# Morpheus_NDO.net
KiCad netlist of a schematic drawn in Altium Designer
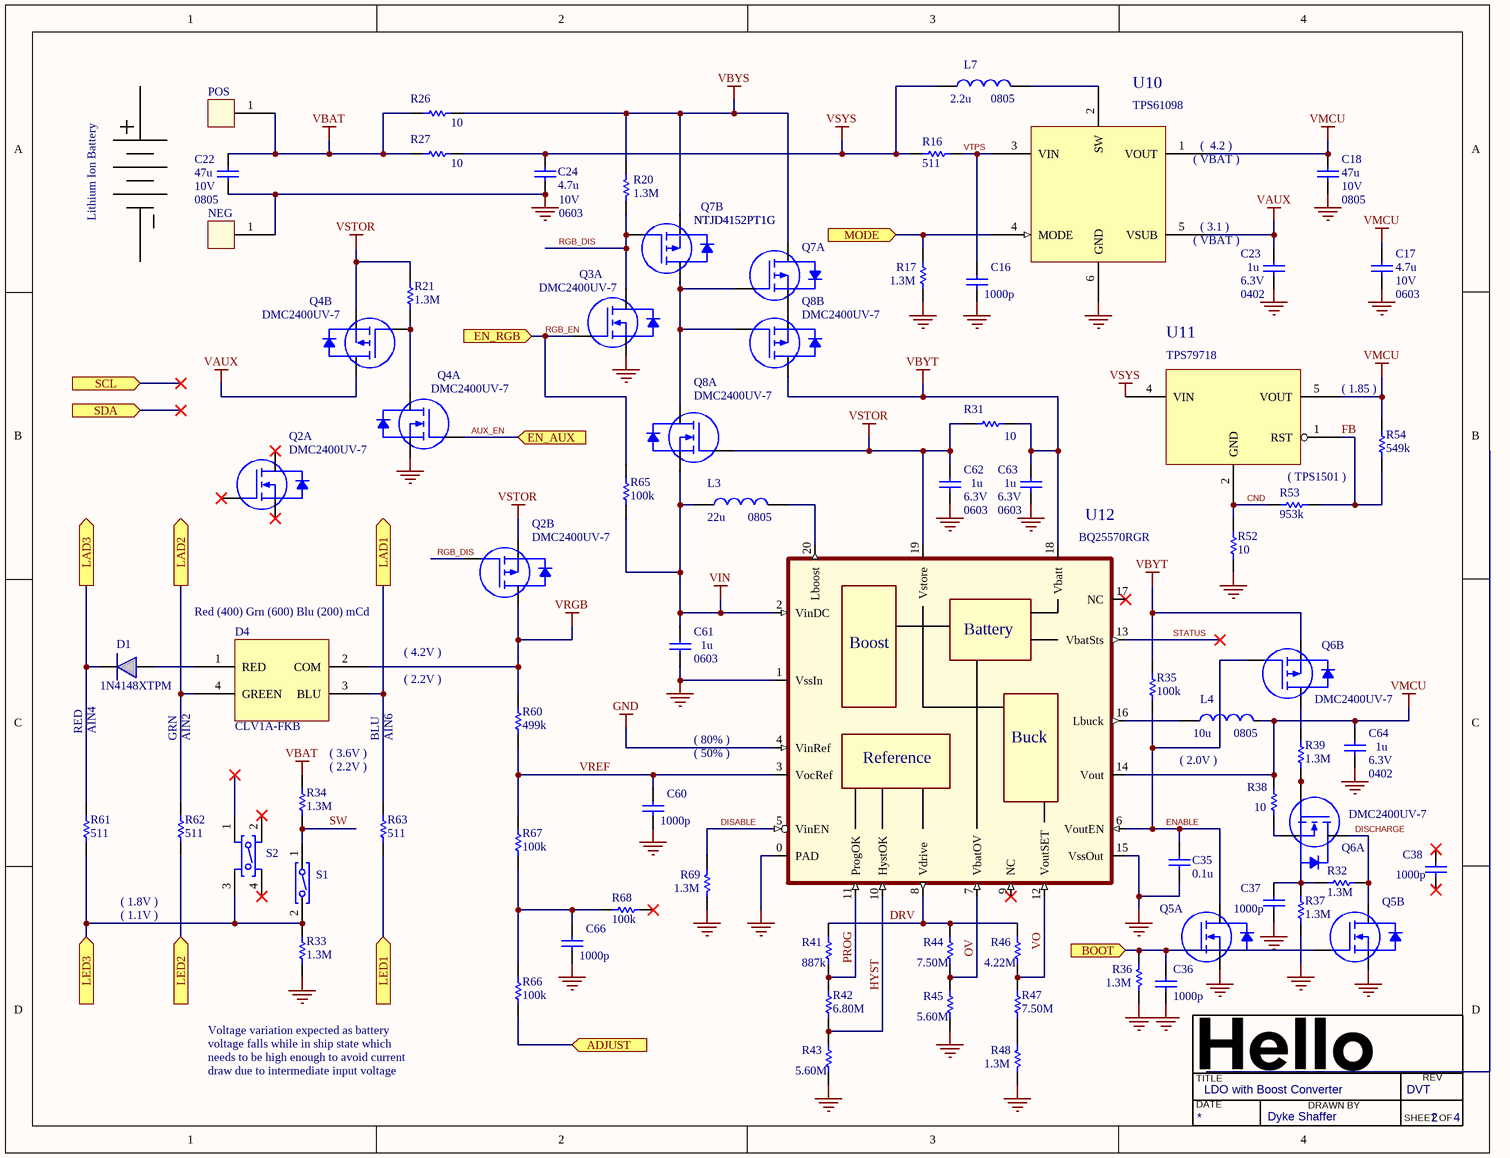
[diagram p0: Morpheus_NDO.SchDoc]

(export (version "E")
  (design (tool "Eeschema 10.0.6"))
  (components
    (comp (ref "C16")
      (value "1000p")
      (footprint "0402C20X24")
      (description "Chip capacitor")
      (fields (field (name "TOLERANCE") "10%") (field (name "VOLTAGE") "50V"))
      (libsource (lib "Hello") (part "C_1000p_10_50_X7R_0402"))
    )
    (comp (ref "C17")
      (value "4.7u")
      (footprint "CAP0603_SENSE_DVT")
      (description "Chip capacitor")
      (fields (field (name "SIZE") "0603") (field (name "TOLERANCE") "20%") (field (name "VOLTAGE") "10V"))
      (libsource (lib "Hello") (part "C_4.7u_20_10_X5R_0603"))
    )
    (comp (ref "C18")
      (value "47u")
      (footprint "0805C45X55")
      (description "Chip capacitor")
      (fields (field (name "SIZE") "0805") (field (name "TOLERANCE") "20%") (field (name "VOLTAGE") "10V"))
      (libsource (lib "Hello") (part "C_47u_20_10_X5R_0805"))
    )
    (comp (ref "C22")
      (value "47u")
      (footprint "0805C45X55")
      (description "Chip capacitor")
      (fields (field (name "SIZE") "0805") (field (name "TOLERANCE") "20%") (field (name "VOLTAGE") "10V"))
      (libsource (lib "Hello") (part "C_47u_20_10_X5R_0805"))
    )
    (comp (ref "C23")
      (value "1u")
      (footprint "CAP0402_SENSE_DVT")
      (description "Chip capacitor")
      (fields (field (name "SIZE") "0402") (field (name "TOLERANCE") "10%") (field (name "VOLTAGE") "6.3V"))
      (libsource (lib "Hello") (part "C_1u_10_6.3_X5R_0402"))
    )
    (comp (ref "C24")
      (value "4.7u")
      (footprint "CAP0603_SENSE_DVT")
      (description "Chip capacitor")
      (fields (field (name "SIZE") "0603") (field (name "TOLERANCE") "20%") (field (name "VOLTAGE") "10V"))
      (libsource (lib "Hello") (part "C_4.7u_20_10_X5R_0603"))
    )
    (comp (ref "C35")
      (value "0.1u")
      (footprint "CAP0402_SENSE_DVT")
      (description "Chip capacitor")
      (fields (field (name "TOLERANCE") "10%") (field (name "VOLTAGE") "50V"))
      (libsource (lib "Hello") (part "C_0.1u_10_50_X7R_0402"))
    )
    (comp (ref "C36")
      (value "1000p")
      (footprint "0402C20X24")
      (description "Chip capacitor")
      (fields (field (name "TOLERANCE") "10%") (field (name "VOLTAGE") "50V"))
      (libsource (lib "Hello") (part "C_1000p_10_50_X7R_0402"))
    )
    (comp (ref "C37")
      (value "1000p")
      (footprint "0402C20X24")
      (description "Chip capacitor")
      (fields (field (name "TOLERANCE") "10%") (field (name "VOLTAGE") "50V"))
      (libsource (lib "Hello") (part "C_1000p_10_50_X7R_0402"))
    )
    (comp (ref "C38")
      (value "1000p")
      (footprint "0402C20X24")
      (description "Chip capacitor")
      (fields (field (name "TOLERANCE") "10%") (field (name "VOLTAGE") "50V"))
      (libsource (lib "Hello") (part "C_1000p_10_50_X7R_0402"))
    )
    (comp (ref "C60")
      (value "1000p")
      (footprint "0402C20X24")
      (description "Chip capacitor")
      (fields (field (name "TOLERANCE") "10%") (field (name "VOLTAGE") "50V"))
      (libsource (lib "Hello") (part "C_1000p_10_50_X7R_0402"))
    )
    (comp (ref "C61")
      (value "1u")
      (footprint "CAP0603_SENSE_DVT")
      (description "Chip capacitor")
      (fields (field (name "SIZE") "0603") (field (name "TOLERANCE") "10%") (field (name "VOLTAGE") "6.3V"))
      (libsource (lib "Hello") (part "C_1u_10_6.3_X5R_0402"))
    )
    (comp (ref "C62")
      (value "1u")
      (footprint "CAP0603_SENSE_DVT")
      (description "Chip capacitor")
      (fields (field (name "SIZE") "0603") (field (name "TOLERANCE") "10%") (field (name "VOLTAGE") "6.3V"))
      (libsource (lib "Hello") (part "C_1u_10_6.3_X5R_0402"))
    )
    (comp (ref "C63")
      (value "1u")
      (footprint "CAP0603_SENSE_DVT")
      (description "Chip capacitor")
      (fields (field (name "SIZE") "0603") (field (name "TOLERANCE") "10%") (field (name "VOLTAGE") "6.3V"))
      (libsource (lib "Hello") (part "C_1u_10_6.3_X5R_0402"))
    )
    (comp (ref "C64")
      (value "1u")
      (footprint "CAP0402_SENSE_DVT")
      (description "Chip capacitor")
      (fields (field (name "SIZE") "0402") (field (name "TOLERANCE") "10%") (field (name "VOLTAGE") "6.3V"))
      (libsource (lib "Hello") (part "C_1u_10_6.3_X5R_0402"))
    )
    (comp (ref "C66")
      (value "1000p")
      (footprint "0402C20X24")
      (description "Chip capacitor")
      (fields (field (name "TOLERANCE") "10%") (field (name "VOLTAGE") "50V"))
      (libsource (lib "Hello") (part "C_1000p_10_50_X7R_0402"))
    )
    (comp (ref "D1")
      (value "1N4148XTPM")
      (footprint "SOD523")
      (description "Silicon diode, 30V 200mA")
      (libsource (lib "Hello") (part "1N4148XTPM"))
    )
    (comp (ref "D4")
      (value "Red (400) Grn (600) Blu (200) mCd")
      (footprint "PLCC150X290P280X320X190-4")
      (description "RGB LED Array")
      (fields (field (name "PN") "CLV1A-FKB") (field (name "Comment") "CLV1A-FKB"))
      (libsource (lib "Hello") (part "CLV1A-FKB"))
    )
    (comp (ref "L3")
      (value "22u")
      (footprint "IND_0805")
      (description "SMD power inductor, 22uH")
      (fields (field (name "TOLERANCE") "20%") (field (name "SIZE") "0805"))
      (libsource (lib "Morpheus_pill") (part "L_22u_0805"))
    )
    (comp (ref "L4")
      (value "10u")
      (footprint "IND_0805")
      (description "SMD power inductor, 10uH")
      (fields (field (name "TOLERANCE") "20%") (field (name "SIZE") "0805"))
      (libsource (lib "Morpheus_pill") (part "L_10u_0805"))
    )
    (comp (ref "L7")
      (value "2.2u")
      (footprint "IND_0805")
      (description "SMD power inductor, 2.2uH")
      (fields (field (name "TOLERANCE") "20%") (field (name "SIZE") "0805"))
      (libsource (lib "Morpheus_pill") (part "L_2.2u_0805"))
    )
    (comp (ref "NEG")
      (value "~")
      (footprint "TP80x50CP")
      (description "Single-pad test point")
      (libsource (lib "Mopd") (part "5016"))
    )
    (comp (ref "POS")
      (value "~")
      (footprint "TP80x50CP")
      (description "Single-pad test point")
      (libsource (lib "Mopd") (part "5016"))
    )
    (comp (ref "Q2")
      (value "DMC2400UV-7")
      (footprint "SOT-563")
      (description "Dual PN-Channel MOSFET 1.2v drive 20V 0.88A")
      (libsource (lib "") (part "DMC2400UV-7_2"))
    )
    (comp (ref "Q3")
      (value "DMC2400UV-7")
      (footprint "SOT-563")
      (description "Dual PN-Channel MOSFET 1.2v drive 20V 0.88A")
      (libsource (lib "") (part "DMC2400UV-7_2"))
    )
    (comp (ref "Q4")
      (value "DMC2400UV-7")
      (footprint "SOT-563")
      (description "Dual PN-Channel MOSFET 1.2v drive 20V 0.88A")
      (libsource (lib "Smith_bot") (part "DMC2400UV-7"))
    )
    (comp (ref "Q5")
      (value "DMG6301UDW-7")
      (footprint "SOT-563")
      (libsource (lib "Hello") (part "DMG6301UDW-7"))
    )
    (comp (ref "Q6")
      (value "DMC2400UV-7")
      (footprint "SOT-563")
      (description "Dual PN-Channel MOSFET 1.2v drive 20V 0.88A")
      (libsource (lib "Smith_bot") (part "DMC2400UV-7"))
    )
    (comp (ref "Q7")
      (value "NTJD4152PT1G")
      (footprint "SOT-563")
      (description "Dual P-Channel MOSFET 1.2v drive 20V 0.88A")
      (libsource (lib "Smith_gen") (part "NTJD4152PT1G"))
    )
    (comp (ref "Q8")
      (value "DMC2400UV-7")
      (footprint "SOT-563")
      (description "Dual PN-Channel MOSFET 1.2v drive 20V 0.88A")
      (libsource (lib "Smith_bot") (part "DMC2400UV-7"))
    )
    (comp (ref "R16")
      (value "511")
      (footprint "RES0402_SENSE_DVT")
      (description "Chip Resistor")
      (fields (field (name "TOLERANCE") "1 %") (field (name "POWER") "0.1 W"))
      (libsource (lib "Hello") (part "R_511_1_0.1_0402"))
    )
    (comp (ref "R17")
      (value "1.3M")
      (footprint "RES0402_SENSE_DVT")
      (description "Chip Resistor")
      (fields (field (name "TOLERANCE") "5 %") (field (name "POWER") "0.1 W"))
      (libsource (lib "Hello") (part "R_1.3M_5_0.1_0402"))
    )
    (comp (ref "R20")
      (value "1.3M")
      (footprint "RES0402_SENSE_DVT")
      (description "Chip Resistor")
      (fields (field (name "TOLERANCE") "5 %") (field (name "POWER") "0.1 W"))
      (libsource (lib "Hello") (part "R_1.3M_5_0.1_0402"))
    )
    (comp (ref "R21")
      (value "1.3M")
      (footprint "RES0402_SENSE_DVT")
      (description "Chip Resistor")
      (fields (field (name "TOLERANCE") "5 %") (field (name "POWER") "0.1 W"))
      (libsource (lib "Hello") (part "R_1.3M_5_0.1_0402"))
    )
    (comp (ref "R26")
      (value "10")
      (footprint "RES0402_SENSE_DVT")
      (description "Chip Resistor")
      (fields (field (name "TOLERANCE") "1 %") (field (name "POWER") "0.1 W"))
      (libsource (lib "Hello") (part "R_10_1_0.1_0402"))
    )
    (comp (ref "R27")
      (value "10")
      (footprint "RES0402_SENSE_DVT")
      (description "Chip Resistor")
      (fields (field (name "TOLERANCE") "1 %") (field (name "POWER") "0.1 W"))
      (libsource (lib "Hello") (part "R_10_1_0.1_0402"))
    )
    (comp (ref "R31")
      (value "10")
      (footprint "RES0402_SENSE_DVT")
      (description "Chip Resistor")
      (fields (field (name "TOLERANCE") "1 %") (field (name "POWER") "0.1 W"))
      (libsource (lib "Hello") (part "R_10_1_0.1_0402"))
    )
    (comp (ref "R32")
      (value "1.3M")
      (footprint "RES0402_SENSE_DVT")
      (description "Chip Resistor")
      (fields (field (name "TOLERANCE") "5 %") (field (name "POWER") "0.1 W"))
      (libsource (lib "Hello") (part "R_1.3M_5_0.1_0402"))
    )
    (comp (ref "R33")
      (value "1.3M")
      (footprint "RES0402_SENSE_DVT")
      (description "Chip Resistor")
      (fields (field (name "TOLERANCE") "5 %") (field (name "POWER") "0.1 W"))
      (libsource (lib "Hello") (part "R_1.3M_5_0.1_0402"))
    )
    (comp (ref "R34")
      (value "1.3M")
      (footprint "RES0402_SENSE_DVT")
      (description "Chip Resistor")
      (fields (field (name "TOLERANCE") "5 %") (field (name "POWER") "0.1 W"))
      (libsource (lib "Hello") (part "R_1.3M_5_0.1_0402"))
    )
    (comp (ref "R35")
      (value "100k")
      (footprint "RES0402_SENSE_DVT")
      (description "Chip Resistor")
      (fields (field (name "TOLERANCE") "1 %") (field (name "POWER") "0.1 W"))
      (libsource (lib "Hello") (part "R_100k_1_0.1_0402"))
    )
    (comp (ref "R36")
      (value "1.3M")
      (footprint "RES0402_SENSE_DVT")
      (description "Chip Resistor")
      (fields (field (name "TOLERANCE") "5 %") (field (name "POWER") "0.1 W"))
      (libsource (lib "Hello") (part "R_1.3M_5_0.1_0402"))
    )
    (comp (ref "R37")
      (value "1.3M")
      (footprint "RES0402_SENSE_DVT")
      (description "Chip Resistor")
      (fields (field (name "TOLERANCE") "5 %") (field (name "POWER") "0.1 W"))
      (libsource (lib "Hello") (part "R_1.3M_5_0.1_0402"))
    )
    (comp (ref "R38")
      (value "10")
      (footprint "RES0402_SENSE_DVT")
      (description "Chip Resistor")
      (fields (field (name "TOLERANCE") "1 %") (field (name "POWER") "0.1 W"))
      (libsource (lib "Hello") (part "R_10_1_0.1_0402"))
    )
    (comp (ref "R39")
      (value "1.3M")
      (footprint "RES0402_SENSE_DVT")
      (description "Chip Resistor")
      (fields (field (name "TOLERANCE") "5 %") (field (name "POWER") "0.1 W"))
      (libsource (lib "Hello") (part "R_1.3M_5_0.1_0402"))
    )
    (comp (ref "R41")
      (value "887k")
      (footprint "0402R18X20")
      (description "Chip Resistor")
      (fields (field (name "TOLERANCE") "1 %") (field (name "POWER") "0.1 W"))
      (libsource (lib "Smith_bot") (part "R_887k_1_0.1_0402"))
    )
    (comp (ref "R42")
      (value "6.80M")
      (footprint "0402R18X20")
      (description "Chip Resistor")
      (fields (field (name "TOLERANCE") "1 %") (field (name "POWER") "0.1 W"))
      (libsource (lib "Smith_bot") (part "R_6.80M_1_0.1_0402"))
    )
    (comp (ref "R43")
      (value "5.60M")
      (footprint "0402R18X20")
      (description "Chip Resistor")
      (fields (field (name "TOLERANCE") "1 %") (field (name "POWER") "0.1 W"))
      (libsource (lib "Smith_bot") (part "R_5.60M_1_0.1_0402"))
    )
    (comp (ref "R44")
      (value "7.50M")
      (footprint "0402R18X20")
      (description "Chip Resistor")
      (fields (field (name "TOLERANCE") "1 %") (field (name "POWER") "0.1 W"))
      (libsource (lib "Smith_bot") (part "R_7.50M_1_0.1_0402"))
    )
    (comp (ref "R45")
      (value "5.60M")
      (footprint "0402R18X20")
      (description "Chip Resistor")
      (fields (field (name "TOLERANCE") "1 %") (field (name "POWER") "0.1 W"))
      (libsource (lib "Smith_bot") (part "R_5.60M_1_0.1_0402"))
    )
    (comp (ref "R46")
      (value "4.22M")
      (footprint "0402R18X20")
      (description "Chip Resistor")
      (fields (field (name "TOLERANCE") "1 %") (field (name "POWER") "0.1 W"))
      (libsource (lib "Smith_bot") (part "R_4.22M_1_0.1_0402"))
    )
    (comp (ref "R47")
      (value "7.50M")
      (footprint "0402R18X20")
      (description "Chip Resistor")
      (fields (field (name "TOLERANCE") "1 %") (field (name "POWER") "0.1 W"))
      (libsource (lib "Smith_bot") (part "R_7.50M_1_0.1_0402"))
    )
    (comp (ref "R48")
      (value "1.3M")
      (footprint "0402R18X20")
      (description "Chip Resistor")
      (fields (field (name "TOLERANCE") "5 %") (field (name "POWER") "0.1 W"))
      (libsource (lib "Hello") (part "R_1.3M_5_0.1_0402"))
    )
    (comp (ref "R52")
      (value "10")
      (footprint "RES0402_SENSE_DVT")
      (description "Chip Resistor")
      (fields (field (name "TOLERANCE") "1 %") (field (name "POWER") "0.1 W"))
      (libsource (lib "Hello") (part "R_10_1_0.1_0402"))
    )
    (comp (ref "R53")
      (value "953k")
      (footprint "RES0402_SENSE_DVT")
      (description "Chip Resistor")
      (fields (field (name "TOLERANCE") "1 %") (field (name "POWER") "0.1 W"))
      (libsource (lib "Smith_bot") (part "R_953k_1_0.1_0402"))
    )
    (comp (ref "R54")
      (value "549k")
      (footprint "RES0402_SENSE_DVT")
      (description "Chip Resistor")
      (fields (field (name "TOLERANCE") "1 %") (field (name "POWER") "0.1 W"))
      (libsource (lib "Hello") (part "R_549k_1_0.1_0402"))
    )
    (comp (ref "R60")
      (value "499k")
      (footprint "RES0402_SENSE_DVT")
      (description "Chip Resistor")
      (fields (field (name "TOLERANCE") "1 %") (field (name "POWER") "0.1 W"))
      (libsource (lib "Hello") (part "R_499k_1_0.1_0402"))
    )
    (comp (ref "R61")
      (value "511")
      (footprint "RES0402_SENSE_DVT")
      (description "Chip Resistor")
      (fields (field (name "TOLERANCE") "1 %") (field (name "POWER") "0.1 W"))
      (libsource (lib "Hello") (part "R_511_1_0.1_0402"))
    )
    (comp (ref "R62")
      (value "511")
      (footprint "RES0402_SENSE_DVT")
      (description "Chip Resistor")
      (fields (field (name "TOLERANCE") "1 %") (field (name "POWER") "0.1 W"))
      (libsource (lib "Hello") (part "R_511_1_0.1_0402"))
    )
    (comp (ref "R63")
      (value "511")
      (footprint "RES0402_SENSE_DVT")
      (description "Chip Resistor")
      (fields (field (name "TOLERANCE") "1 %") (field (name "POWER") "0.1 W"))
      (libsource (lib "Hello") (part "R_511_1_0.1_0402"))
    )
    (comp (ref "R65")
      (value "100k")
      (footprint "RES0402_SENSE_DVT")
      (description "Chip Resistor")
      (fields (field (name "TOLERANCE") "1 %") (field (name "POWER") "0.1 W"))
      (libsource (lib "Hello") (part "R_100k_1_0.1_0402"))
    )
    (comp (ref "R66")
      (value "100k")
      (footprint "RES0402_SENSE_DVT")
      (description "Chip Resistor")
      (fields (field (name "TOLERANCE") "1 %") (field (name "POWER") "0.1 W"))
      (libsource (lib "Hello") (part "R_100k_1_0.1_0402"))
    )
    (comp (ref "R67")
      (value "100k")
      (footprint "RES0402_SENSE_DVT")
      (description "Chip Resistor")
      (fields (field (name "TOLERANCE") "1 %") (field (name "POWER") "0.1 W"))
      (libsource (lib "Hello") (part "R_100k_1_0.1_0402"))
    )
    (comp (ref "R68")
      (value "100k")
      (footprint "RES0402_SENSE_DVT")
      (description "Chip Resistor")
      (fields (field (name "TOLERANCE") "1 %") (field (name "POWER") "0.1 W"))
      (libsource (lib "Hello") (part "R_100k_1_0.1_0402"))
    )
    (comp (ref "R69")
      (value "1.3M")
      (footprint "0402R18X20")
      (description "Chip Resistor")
      (fields (field (name "TOLERANCE") "5 %") (field (name "POWER") "0.1 W"))
      (libsource (lib "Hello") (part "R_1.3M_5_0.1_0402"))
    )
    (comp (ref "S1")
      (value "REED_SPST_NO")
      (footprint "REED-10x1.8")
      (description "SWITCH REED SPST NO")
      (libsource (lib "Hello") (part "SW_REED_SPST_NO"))
    )
    (comp (ref "S2")
      (value "REED_SPST_NO")
      (footprint "PLCC350X400P450X450X65-4")
      (description "SWITCH SPST NO")
      (libsource (lib "Smith_top") (part "SW_SPST_NO"))
    )
    (comp (ref "U10")
      (value "TPS61098")
      (footprint "DFN50P150X150X80-6N")
      (description "Boost Converter")
      (libsource (lib "Smith_bot") (part "TPS61098"))
    )
    (comp (ref "U11")
      (value "TPS79718")
      (footprint "SOT65P212X110-5N")
      (description "LDO 1.8V SC70-5")
      (libsource (lib "dykes") (part "TPS79718DCK"))
    )
    (comp (ref "U12")
      (value "BQ25570RGR")
      (footprint "VQFN50P350X350X100-20")
      (libsource (lib "dykes") (part "BQ25570RGR"))
    )
  )
  (nets
    (net (code "1") (name "/ADJUST") (class "Default")
      (node (ref "R66") (pin "1") (pinfunction "1_1") (pintype "passive"))
    )
    (net (code "2") (name "/AUX_EN") (class "Default")
      (node (ref "Q4") (pin "2") (pinfunction "G1_2") (pintype "passive"))
    )
    (net (code "3") (name "/BOOT") (class "Default")
      (node (ref "C36") (pin "2") (pinfunction "2_2") (pintype "passive"))
      (node (ref "Q5") (pin "2") (pinfunction "G1_2") (pintype "passive"))
      (node (ref "Q5") (pin "5") (pinfunction "G2_5") (pintype "passive"))
      (node (ref "R36") (pin "2") (pinfunction "2_2") (pintype "passive"))
    )
    (net (code "4") (name "/CND") (class "Default")
      (node (ref "R52") (pin "2") (pinfunction "2_2") (pintype "passive"))
      (node (ref "R53") (pin "1") (pinfunction "1_1") (pintype "passive"))
      (node (ref "U11") (pin "2") (pinfunction "GND_2") (pintype "power_in"))
    )
    (net (code "5") (name "/DISABLE") (class "Default")
      (node (ref "R69") (pin "2") (pinfunction "2_2") (pintype "passive"))
      (node (ref "U12") (pin "5") (pinfunction "VinEN_5") (pintype "input"))
    )
    (net (code "6") (name "/DISCHARGE") (class "Default")
      (node (ref "Q5") (pin "3") (pinfunction "D2_3") (pintype "passive"))
      (node (ref "Q6") (pin "6") (pinfunction "D1_6") (pintype "passive"))
      (node (ref "R32") (pin "1") (pinfunction "1_1") (pintype "passive"))
    )
    (net (code "7") (name "/DRV") (class "Default")
      (node (ref "R41") (pin "2") (pinfunction "2_2") (pintype "passive"))
      (node (ref "R44") (pin "2") (pinfunction "2_2") (pintype "passive"))
      (node (ref "R46") (pin "2") (pinfunction "2_2") (pintype "passive"))
      (node (ref "U12") (pin "8") (pinfunction "Vdrive_8") (pintype "output"))
    )
    (net (code "8") (name "/ENABLE") (class "Default")
      (node (ref "C35") (pin "2") (pinfunction "2_2") (pintype "passive"))
      (node (ref "Q5") (pin "6") (pinfunction "D1_6") (pintype "passive"))
      (node (ref "Q6") (pin "5") (pinfunction "G2_5") (pintype "passive"))
      (node (ref "R35") (pin "1") (pinfunction "1_1") (pintype "passive"))
      (node (ref "U12") (pin "6") (pinfunction "VoutEN_6") (pintype "input"))
    )
    (net (code "9") (name "/FB") (class "Default")
      (node (ref "R53") (pin "2") (pinfunction "2_2") (pintype "passive"))
      (node (ref "R54") (pin "1") (pinfunction "1_1") (pintype "passive"))
      (node (ref "U11") (pin "1") (pinfunction "RST_1") (pintype "open_collector"))
    )
    (net (code "10") (name "/HYST") (class "Default")
      (node (ref "R42") (pin "1") (pinfunction "1_1") (pintype "passive"))
      (node (ref "R43") (pin "2") (pinfunction "2_2") (pintype "passive"))
      (node (ref "U12") (pin "10") (pinfunction "HystOK_10") (pintype "input"))
    )
    (net (code "11") (name "/LAD1") (class "Default")
      (node (ref "D4") (pin "3") (pinfunction "BLU_3") (pintype "passive"))
      (node (ref "R63") (pin "2") (pinfunction "2_2") (pintype "passive"))
    )
    (net (code "12") (name "/LAD2") (class "Default")
      (node (ref "D4") (pin "4") (pinfunction "GREEN_4") (pintype "passive"))
      (node (ref "R62") (pin "2") (pinfunction "2_2") (pintype "passive"))
    )
    (net (code "13") (name "/LAD3") (class "Default")
      (node (ref "D1") (pin "1") (pinfunction "Cathode_1") (pintype "passive"))
      (node (ref "R61") (pin "2") (pinfunction "2_2") (pintype "passive"))
    )
    (net (code "14") (name "/LED1") (class "Default")
      (node (ref "R63") (pin "1") (pinfunction "1_1") (pintype "passive"))
    )
    (net (code "15") (name "/LED2") (class "Default")
      (node (ref "R62") (pin "1") (pinfunction "1_1") (pintype "passive"))
    )
    (net (code "16") (name "/LED3") (class "Default")
      (node (ref "R33") (pin "2") (pinfunction "2_2") (pintype "passive"))
      (node (ref "R61") (pin "1") (pinfunction "1_1") (pintype "passive"))
      (node (ref "S1") (pin "2") (pinfunction "2_2") (pintype "passive"))
      (node (ref "S2") (pin "3") (pinfunction "3_3") (pintype "passive"))
    )
    (net (code "17") (name "/MODE") (class "Default")
      (node (ref "R17") (pin "1") (pinfunction "1_1") (pintype "passive"))
      (node (ref "U10") (pin "4") (pinfunction "MODE_4") (pintype "input"))
    )
    (net (code "18") (name "/OV") (class "Default")
      (node (ref "R44") (pin "1") (pinfunction "1_1") (pintype "passive"))
      (node (ref "R45") (pin "2") (pinfunction "2_2") (pintype "passive"))
      (node (ref "U12") (pin "7") (pinfunction "VbatOV_7") (pintype "input"))
    )
    (net (code "19") (name "/PROG") (class "Default")
      (node (ref "R41") (pin "1") (pinfunction "1_1") (pintype "passive"))
      (node (ref "R42") (pin "2") (pinfunction "2_2") (pintype "passive"))
      (node (ref "U12") (pin "11") (pinfunction "ProgOK_11") (pintype "input"))
    )
    (net (code "20") (name "/RGB_DIS") (class "Default")
      (node (ref "Q2") (pin "5") (pinfunction "G2_5") (pintype "passive"))
      (node (ref "Q3") (pin "6") (pinfunction "D1_6") (pintype "passive"))
      (node (ref "Q7") (pin "5") (pinfunction "G2_5") (pintype "passive"))
      (node (ref "R20") (pin "1") (pinfunction "1_1") (pintype "passive"))
    )
    (net (code "21") (name "/RGB_EN") (class "Default")
      (node (ref "Q3") (pin "2") (pinfunction "G1_2") (pintype "passive"))
      (node (ref "R65") (pin "2") (pinfunction "2_2") (pintype "passive"))
    )
    (net (code "24") (name "/STATUS") (class "Default")
      (node (ref "U12") (pin "13") (pinfunction "VbatSts_13") (pintype "output+no_connect"))
    )
    (net (code "25") (name "/SW") (class "Default")
      (node (ref "R34") (pin "1") (pinfunction "1_1") (pintype "passive"))
      (node (ref "S1") (pin "1") (pinfunction "1_1") (pintype "passive"))
    )
    (net (code "26") (name "/VO") (class "Default")
      (node (ref "R46") (pin "1") (pinfunction "1_1") (pintype "passive"))
      (node (ref "R47") (pin "2") (pinfunction "2_2") (pintype "passive"))
      (node (ref "U12") (pin "12") (pinfunction "VoutSET_12") (pintype "input"))
    )
    (net (code "27") (name "/VREF") (class "Default")
      (node (ref "C60") (pin "2") (pinfunction "2_2") (pintype "passive"))
      (node (ref "R60") (pin "1") (pinfunction "1_1") (pintype "passive"))
      (node (ref "R67") (pin "2") (pinfunction "2_2") (pintype "passive"))
      (node (ref "U12") (pin "3") (pinfunction "VocRef_3") (pintype "passive"))
    )
    (net (code "28") (name "/VTPS") (class "Default")
      (node (ref "C16") (pin "2") (pinfunction "2_2") (pintype "passive"))
      (node (ref "R16") (pin "1") (pinfunction "1_1") (pintype "passive"))
      (node (ref "U10") (pin "3") (pinfunction "VIN_3") (pintype "power_in"))
    )
    (net (code "29") (name "GND") (class "Default")
      (node (ref "C16") (pin "1") (pinfunction "1_1") (pintype "passive"))
      (node (ref "C17") (pin "1") (pinfunction "1_1") (pintype "passive"))
      (node (ref "C18") (pin "1") (pinfunction "1_1") (pintype "passive"))
      (node (ref "C22") (pin "1") (pinfunction "1_1") (pintype "passive"))
      (node (ref "C23") (pin "1") (pinfunction "1_1") (pintype "passive"))
      (node (ref "C24") (pin "1") (pinfunction "1_1") (pintype "passive"))
      (node (ref "C35") (pin "1") (pinfunction "1_1") (pintype "passive"))
      (node (ref "C36") (pin "1") (pinfunction "1_1") (pintype "passive"))
      (node (ref "C37") (pin "1") (pinfunction "1_1") (pintype "passive"))
      (node (ref "C60") (pin "1") (pinfunction "1_1") (pintype "passive"))
      (node (ref "C61") (pin "1") (pinfunction "1_1") (pintype "passive"))
      (node (ref "C62") (pin "1") (pinfunction "1_1") (pintype "passive"))
      (node (ref "C63") (pin "1") (pinfunction "1_1") (pintype "passive"))
      (node (ref "C64") (pin "1") (pinfunction "1_1") (pintype "passive"))
      (node (ref "C66") (pin "1") (pinfunction "1_1") (pintype "passive"))
      (node (ref "NEG") (pin "1") (pinfunction "1_1") (pintype "passive"))
      (node (ref "Q3") (pin "1") (pinfunction "S1_1") (pintype "passive"))
      (node (ref "Q4") (pin "1") (pinfunction "S1_1") (pintype "passive"))
      (node (ref "Q5") (pin "1") (pinfunction "S1_1") (pintype "passive"))
      (node (ref "Q5") (pin "4") (pinfunction "S2_4") (pintype "passive"))
      (node (ref "R17") (pin "2") (pinfunction "2_2") (pintype "passive"))
      (node (ref "R33") (pin "1") (pinfunction "1_1") (pintype "passive"))
      (node (ref "R36") (pin "1") (pinfunction "1_1") (pintype "passive"))
      (node (ref "R37") (pin "1") (pinfunction "1_1") (pintype "passive"))
      (node (ref "R43") (pin "1") (pinfunction "1_1") (pintype "passive"))
      (node (ref "R45") (pin "1") (pinfunction "1_1") (pintype "passive"))
      (node (ref "R48") (pin "1") (pinfunction "1_1") (pintype "passive"))
      (node (ref "R52") (pin "1") (pinfunction "1_1") (pintype "passive"))
      (node (ref "R69") (pin "1") (pinfunction "1_1") (pintype "passive"))
      (node (ref "U10") (pin "6") (pinfunction "GND_6") (pintype "power_in"))
      (node (ref "U12") (pin "0") (pinfunction "PAD_0") (pintype "passive"))
      (node (ref "U12") (pin "1") (pinfunction "VssIn_1") (pintype "power_in"))
      (node (ref "U12") (pin "15") (pinfunction "VssOut_15") (pintype "power_in"))
      (node (ref "U12") (pin "4") (pinfunction "VinRef_4") (pintype "input"))
    )
    (net (code "30") (name "Net-(C66-Pad2)") (class "Default")
      (node (ref "C66") (pin "2") (pinfunction "2_2") (pintype "passive"))
      (node (ref "R66") (pin "2") (pinfunction "2_2") (pintype "passive"))
      (node (ref "R67") (pin "1") (pinfunction "1_1") (pintype "passive"))
      (node (ref "R68") (pin "2") (pinfunction "2_2") (pintype "passive"))
    )
    (net (code "31") (name "Net-(D1-Anode)") (class "Default")
      (node (ref "D1") (pin "2") (pinfunction "Anode_2") (pintype "passive"))
      (node (ref "D4") (pin "1") (pinfunction "RED_1") (pintype "passive"))
    )
    (net (code "32") (name "Net-(Q4A-D1)") (class "Default")
      (node (ref "Q4") (pin "5") (pinfunction "G2_5") (pintype "passive"))
      (node (ref "Q4") (pin "6") (pinfunction "D1_6") (pintype "passive"))
      (node (ref "R21") (pin "1") (pinfunction "1_1") (pintype "passive"))
    )
    (net (code "33") (name "Net-(Q6A-G1)") (class "Default")
      (node (ref "C37") (pin "2") (pinfunction "2_2") (pintype "passive"))
      (node (ref "Q6") (pin "2") (pinfunction "G1_2") (pintype "passive"))
      (node (ref "R32") (pin "2") (pinfunction "2_2") (pintype "passive"))
      (node (ref "R37") (pin "2") (pinfunction "2_2") (pintype "passive"))
      (node (ref "R39") (pin "1") (pinfunction "1_1") (pintype "passive"))
    )
    (net (code "34") (name "Net-(Q6A-S1)") (class "Default")
      (node (ref "Q6") (pin "1") (pinfunction "S1_1") (pintype "passive"))
      (node (ref "R38") (pin "1") (pinfunction "1_1") (pintype "passive"))
    )
    (net (code "35") (name "Net-(Q6B-D2)") (class "Default")
      (node (ref "Q6") (pin "3") (pinfunction "D2_3") (pintype "passive"))
      (node (ref "R39") (pin "2") (pinfunction "2_2") (pintype "passive"))
    )
    (net (code "36") (name "Net-(Q7A-G1)") (class "Default")
      (node (ref "Q7") (pin "2") (pinfunction "G1_2") (pintype "passive"))
      (node (ref "Q7") (pin "3") (pinfunction "D2_3") (pintype "passive"))
      (node (ref "Q8") (pin "5") (pinfunction "G2_5") (pintype "passive"))
      (node (ref "Q8") (pin "6") (pinfunction "D1_6") (pintype "passive"))
    )
    (net (code "37") (name "Net-(Q7A-S1)") (class "Default")
      (node (ref "Q7") (pin "1") (pinfunction "S1_1") (pintype "passive"))
      (node (ref "Q8") (pin "4") (pinfunction "S2_4") (pintype "passive"))
    )
    (net (code "38") (name "Net-(R47-Pad1)") (class "Default")
      (node (ref "R47") (pin "1") (pinfunction "1_1") (pintype "passive"))
      (node (ref "R48") (pin "2") (pinfunction "2_2") (pintype "passive"))
    )
    (net (code "39") (name "Net-(U10-SW)") (class "Default")
      (node (ref "L7") (pin "1") (pintype "passive"))
      (node (ref "U10") (pin "2") (pinfunction "SW_2") (pintype "passive"))
    )
    (net (code "40") (name "Net-(U12-Lboost)") (class "Default")
      (node (ref "L3") (pin "1") (pintype "passive"))
      (node (ref "U12") (pin "20") (pinfunction "Lboost_20") (pintype "output"))
    )
    (net (code "41") (name "Net-(U12-Lbuck)") (class "Default")
      (node (ref "L4") (pin "2") (pintype "passive"))
      (node (ref "U12") (pin "16") (pinfunction "Lbuck_16") (pintype "output"))
    )
    (net (code "42") (name "VAUX") (class "Default")
      (node (ref "C23") (pin "2") (pinfunction "2_2") (pintype "passive"))
      (node (ref "Q4") (pin "3") (pinfunction "D2_3") (pintype "passive"))
      (node (ref "U10") (pin "5") (pinfunction "VSUB_5") (pintype "power_in"))
    )
    (net (code "43") (name "VBAT") (class "Default")
      (node (ref "C22") (pin "2") (pinfunction "2_2") (pintype "passive"))
      (node (ref "POS") (pin "1") (pinfunction "1_1") (pintype "passive"))
      (node (ref "R26") (pin "1") (pinfunction "1_1") (pintype "passive"))
      (node (ref "R27") (pin "1") (pinfunction "1_1") (pintype "passive"))
      (node (ref "R34") (pin "2") (pinfunction "2_2") (pintype "passive"))
    )
    (net (code "44") (name "VBYS") (class "Default")
      (node (ref "Q7") (pin "4") (pinfunction "S2_4") (pintype "passive"))
      (node (ref "Q7") (pin "6") (pinfunction "D1_6") (pintype "passive"))
      (node (ref "R20") (pin "2") (pinfunction "2_2") (pintype "passive"))
      (node (ref "R26") (pin "2") (pinfunction "2_2") (pintype "passive"))
    )
    (net (code "45") (name "VBYT") (class "Default")
      (node (ref "C63") (pin "2") (pinfunction "2_2") (pintype "passive"))
      (node (ref "Q6") (pin "4") (pinfunction "S2_4") (pintype "passive"))
      (node (ref "Q8") (pin "3") (pinfunction "D2_3") (pintype "passive"))
      (node (ref "R31") (pin "1") (pinfunction "1_1") (pintype "passive"))
      (node (ref "R35") (pin "2") (pinfunction "2_2") (pintype "passive"))
      (node (ref "U12") (pin "18") (pinfunction "Vbatt_18") (pintype "power_in"))
    )
    (net (code "46") (name "VIN") (class "Default")
      (node (ref "C61") (pin "2") (pinfunction "2_2") (pintype "passive"))
      (node (ref "L3") (pin "2") (pintype "passive"))
      (node (ref "Q8") (pin "1") (pinfunction "S1_1") (pintype "passive"))
      (node (ref "R65") (pin "1") (pinfunction "1_1") (pintype "passive"))
      (node (ref "U12") (pin "2") (pinfunction "VinDC_2") (pintype "input"))
    )
    (net (code "47") (name "VMCU") (class "Default")
      (node (ref "C17") (pin "2") (pinfunction "2_2") (pintype "passive"))
      (node (ref "C18") (pin "2") (pinfunction "2_2") (pintype "passive"))
      (node (ref "C64") (pin "2") (pinfunction "2_2") (pintype "passive"))
      (node (ref "L4") (pin "1") (pintype "passive"))
      (node (ref "R38") (pin "2") (pinfunction "2_2") (pintype "passive"))
      (node (ref "R54") (pin "2") (pinfunction "2_2") (pintype "passive"))
      (node (ref "U10") (pin "1") (pinfunction "VOUT_1") (pintype "power_in"))
      (node (ref "U11") (pin "5") (pinfunction "VOUT_5") (pintype "power_in"))
      (node (ref "U12") (pin "14") (pinfunction "Vout_14") (pintype "power_in"))
    )
    (net (code "48") (name "VRGB") (class "Default")
      (node (ref "D4") (pin "2") (pinfunction "COM_2") (pintype "passive"))
      (node (ref "Q2") (pin "3") (pinfunction "D2_3") (pintype "passive"))
      (node (ref "R60") (pin "2") (pinfunction "2_2") (pintype "passive"))
    )
    (net (code "49") (name "VSTOR") (class "Default")
      (node (ref "C62") (pin "2") (pinfunction "2_2") (pintype "passive"))
      (node (ref "Q2") (pin "4") (pinfunction "S2_4") (pintype "passive"))
      (node (ref "Q4") (pin "4") (pinfunction "S2_4") (pintype "passive"))
      (node (ref "Q8") (pin "2") (pinfunction "G1_2") (pintype "passive"))
      (node (ref "R21") (pin "2") (pinfunction "2_2") (pintype "passive"))
      (node (ref "R31") (pin "2") (pinfunction "2_2") (pintype "passive"))
      (node (ref "U12") (pin "19") (pinfunction "Vstore_19") (pintype "power_in"))
    )
    (net (code "50") (name "VSYS") (class "Default")
      (node (ref "C24") (pin "2") (pinfunction "2_2") (pintype "passive"))
      (node (ref "L7") (pin "2") (pintype "passive"))
      (node (ref "R16") (pin "2") (pinfunction "2_2") (pintype "passive"))
      (node (ref "R27") (pin "2") (pinfunction "2_2") (pintype "passive"))
      (node (ref "U11") (pin "4") (pinfunction "VIN_4") (pintype "power_in"))
    )
    (net (code "51") (name "unconnected-(C38-Pad1)") (class "Default")
      (node (ref "C38") (pin "1") (pinfunction "1_1") (pintype "passive+no_connect"))
    )
    (net (code "52") (name "unconnected-(C38-Pad2)") (class "Default")
      (node (ref "C38") (pin "2") (pinfunction "2_2") (pintype "passive+no_connect"))
    )
    (net (code "53") (name "unconnected-(Q2A-D1-Pad6)") (class "Default")
      (node (ref "Q2") (pin "6") (pinfunction "D1_6") (pintype "passive+no_connect"))
    )
    (net (code "54") (name "unconnected-(Q2A-G1-Pad2)") (class "Default")
      (node (ref "Q2") (pin "2") (pinfunction "G1_2") (pintype "passive+no_connect"))
    )
    (net (code "55") (name "unconnected-(Q2A-S1-Pad1)") (class "Default")
      (node (ref "Q2") (pin "1") (pinfunction "S1_1") (pintype "passive+no_connect"))
    )
    (net (code "56") (name "unconnected-(R68-Pad1)") (class "Default")
      (node (ref "R68") (pin "1") (pinfunction "1_1") (pintype "passive+no_connect"))
    )
    (net (code "57") (name "unconnected-(S2-Pad1)") (class "Default")
      (node (ref "S2") (pin "1") (pinfunction "1_1") (pintype "passive+no_connect"))
    )
    (net (code "58") (name "unconnected-(S2-Pad2)") (class "Default")
      (node (ref "S2") (pin "2") (pinfunction "2_2") (pintype "passive+no_connect"))
    )
    (net (code "59") (name "unconnected-(S2-Pad4)") (class "Default")
      (node (ref "S2") (pin "4") (pinfunction "4_4") (pintype "passive+no_connect"))
    )
    (net (code "60") (name "unconnected-(U12-NC-Pad9)") (class "Default")
      (node (ref "U12") (pin "9") (pinfunction "NC_9") (pintype "input+no_connect"))
    )
    (net (code "61") (name "unconnected-(U12-NC-Pad17)") (class "Default")
      (node (ref "U12") (pin "17") (pinfunction "NC_17") (pintype "power_in+no_connect"))
    )
  )
)
